# meca_2018.net
KiCad netlist of a schematic drawn in EAGLE
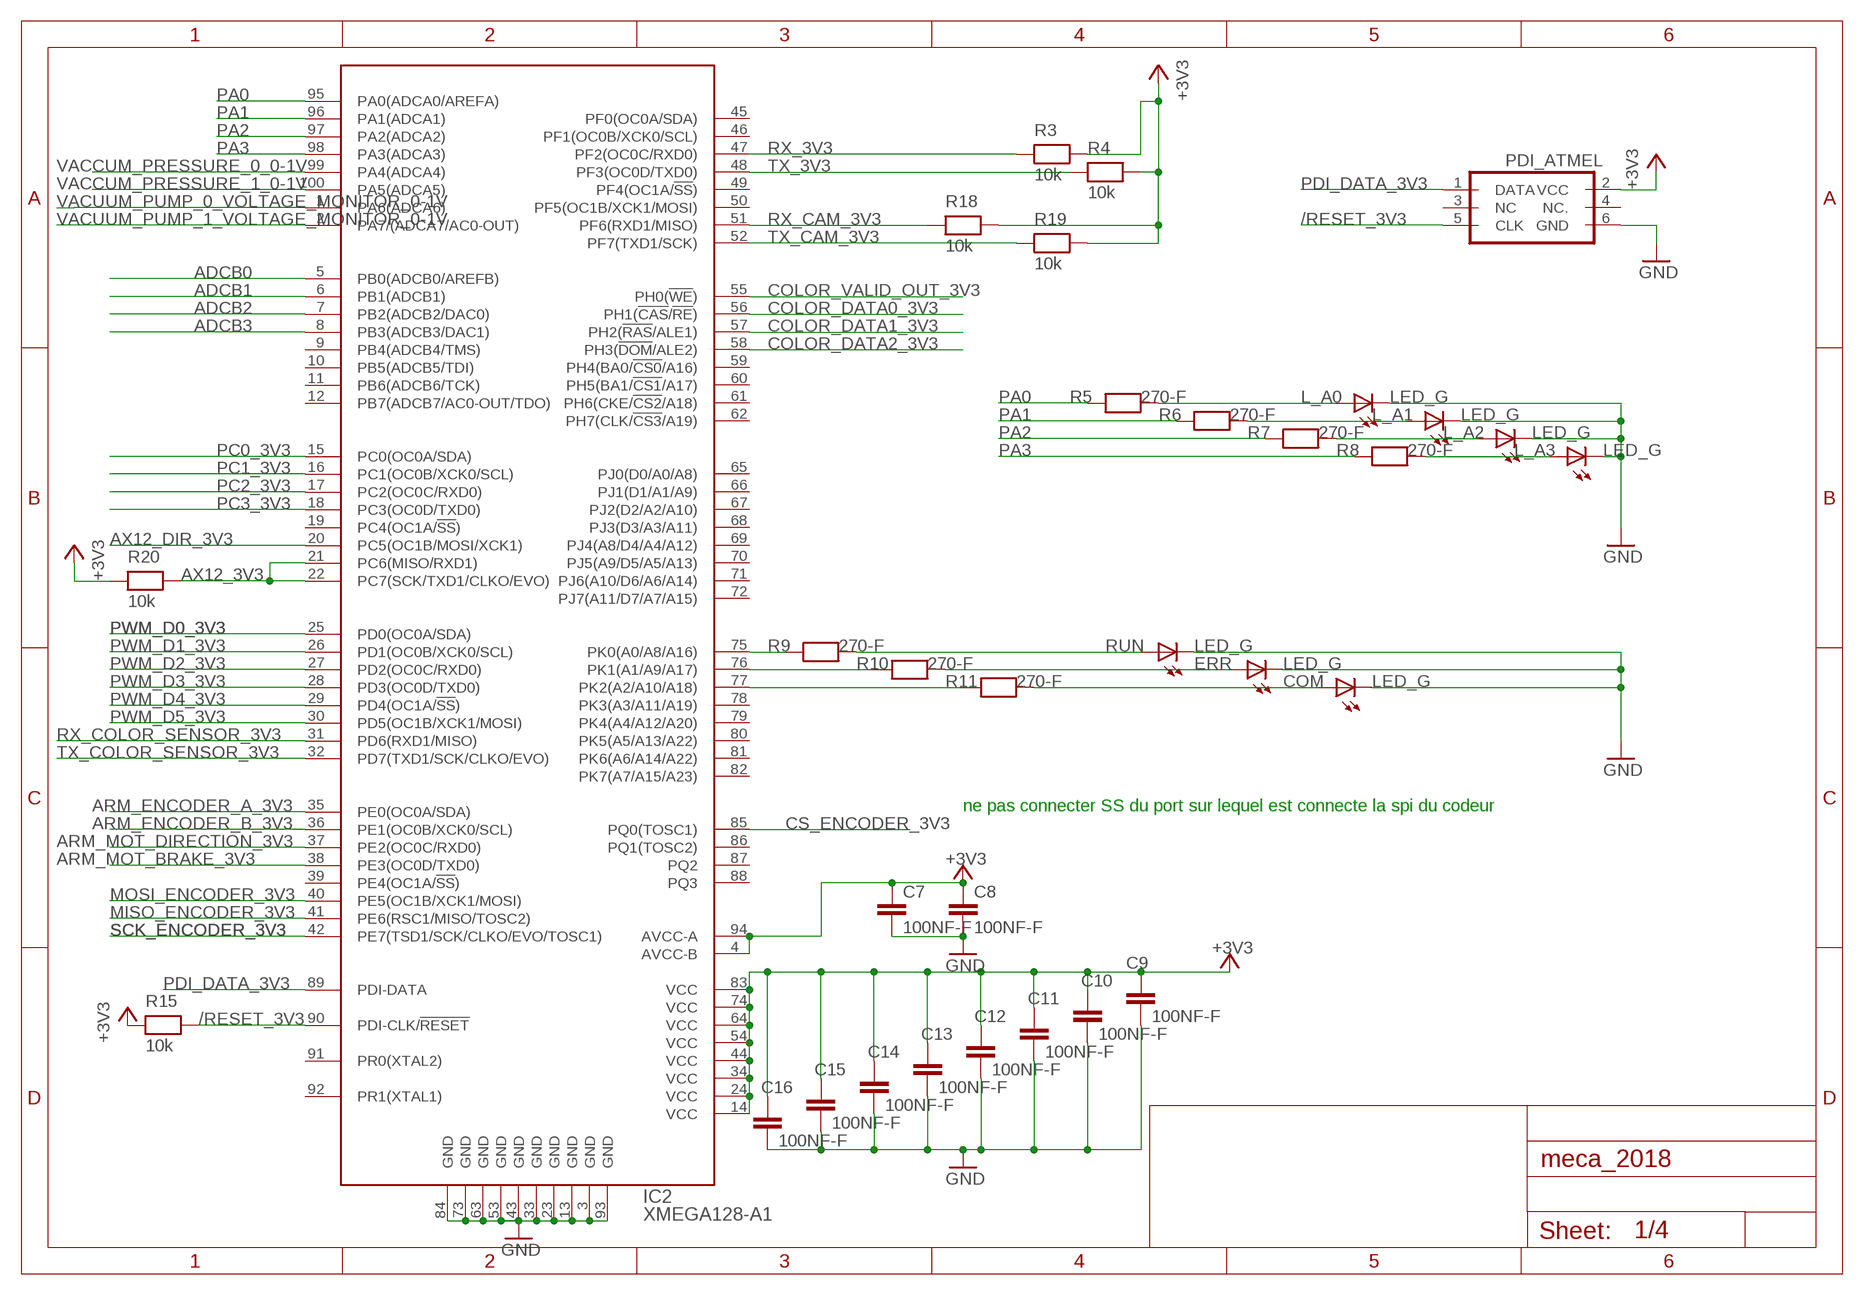
[diagram p0: schematic, sheet 1]
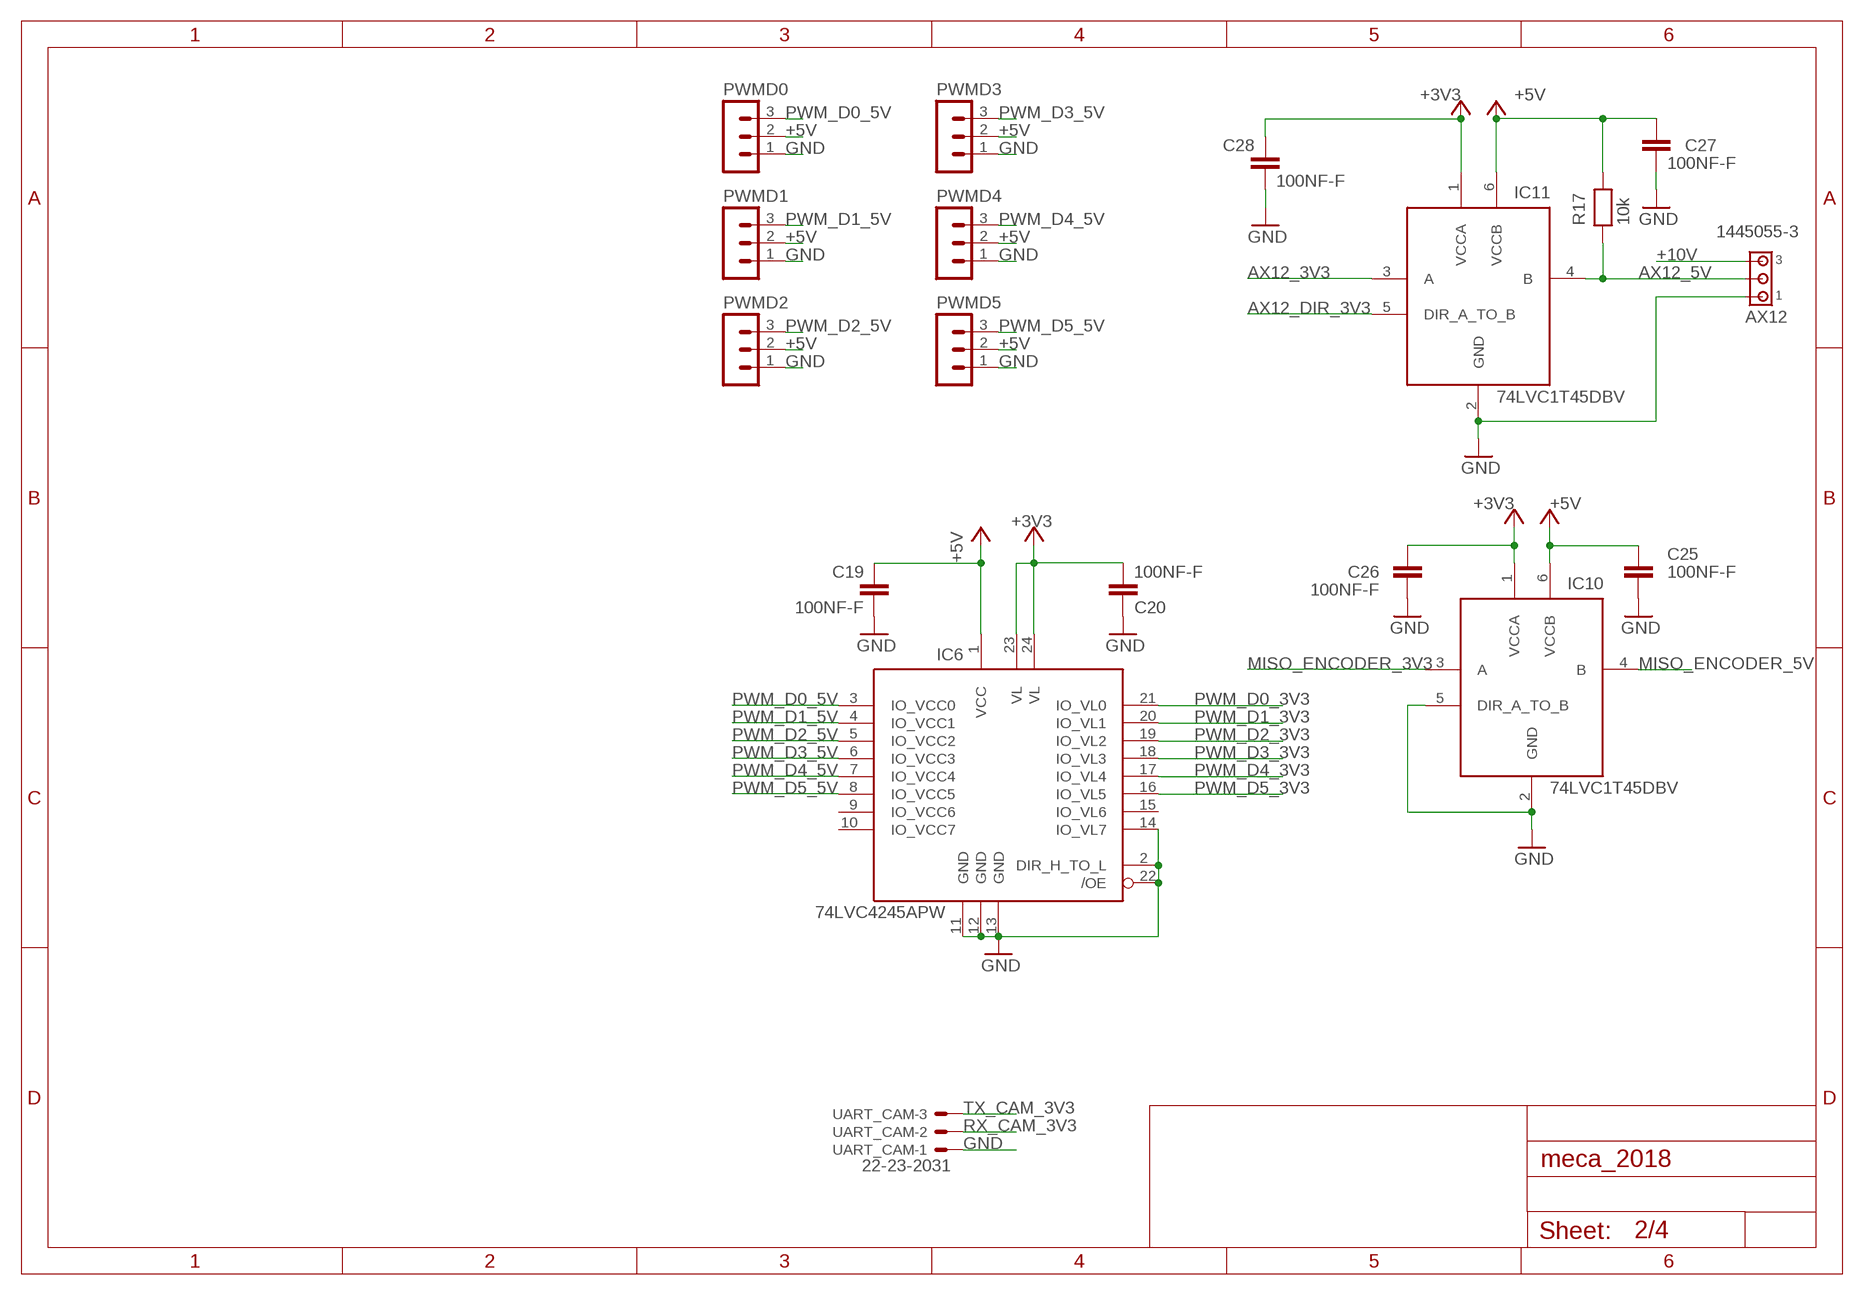
[diagram p1: schematic, sheet 2]
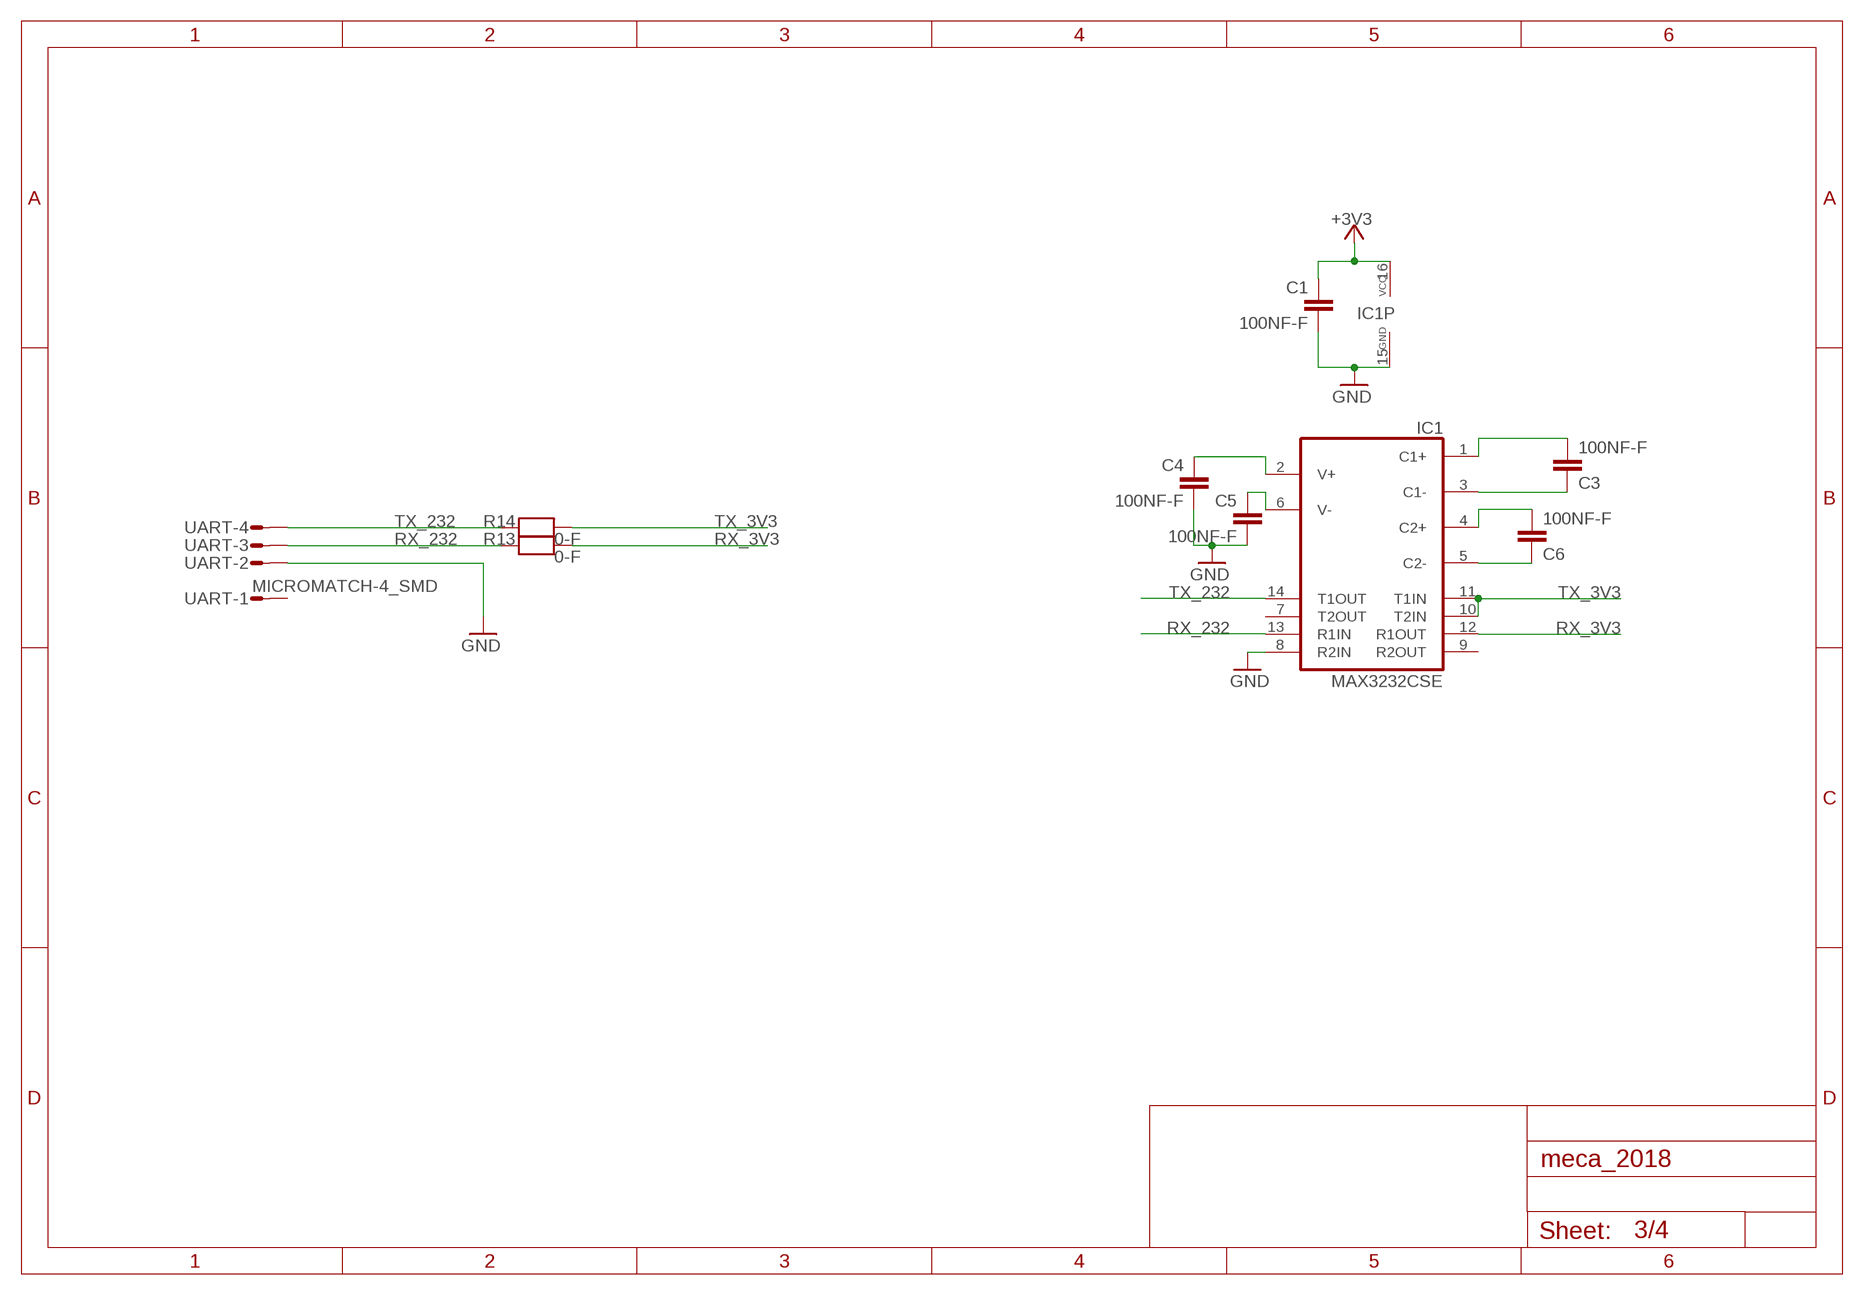
[diagram p2: schematic, sheet 3]
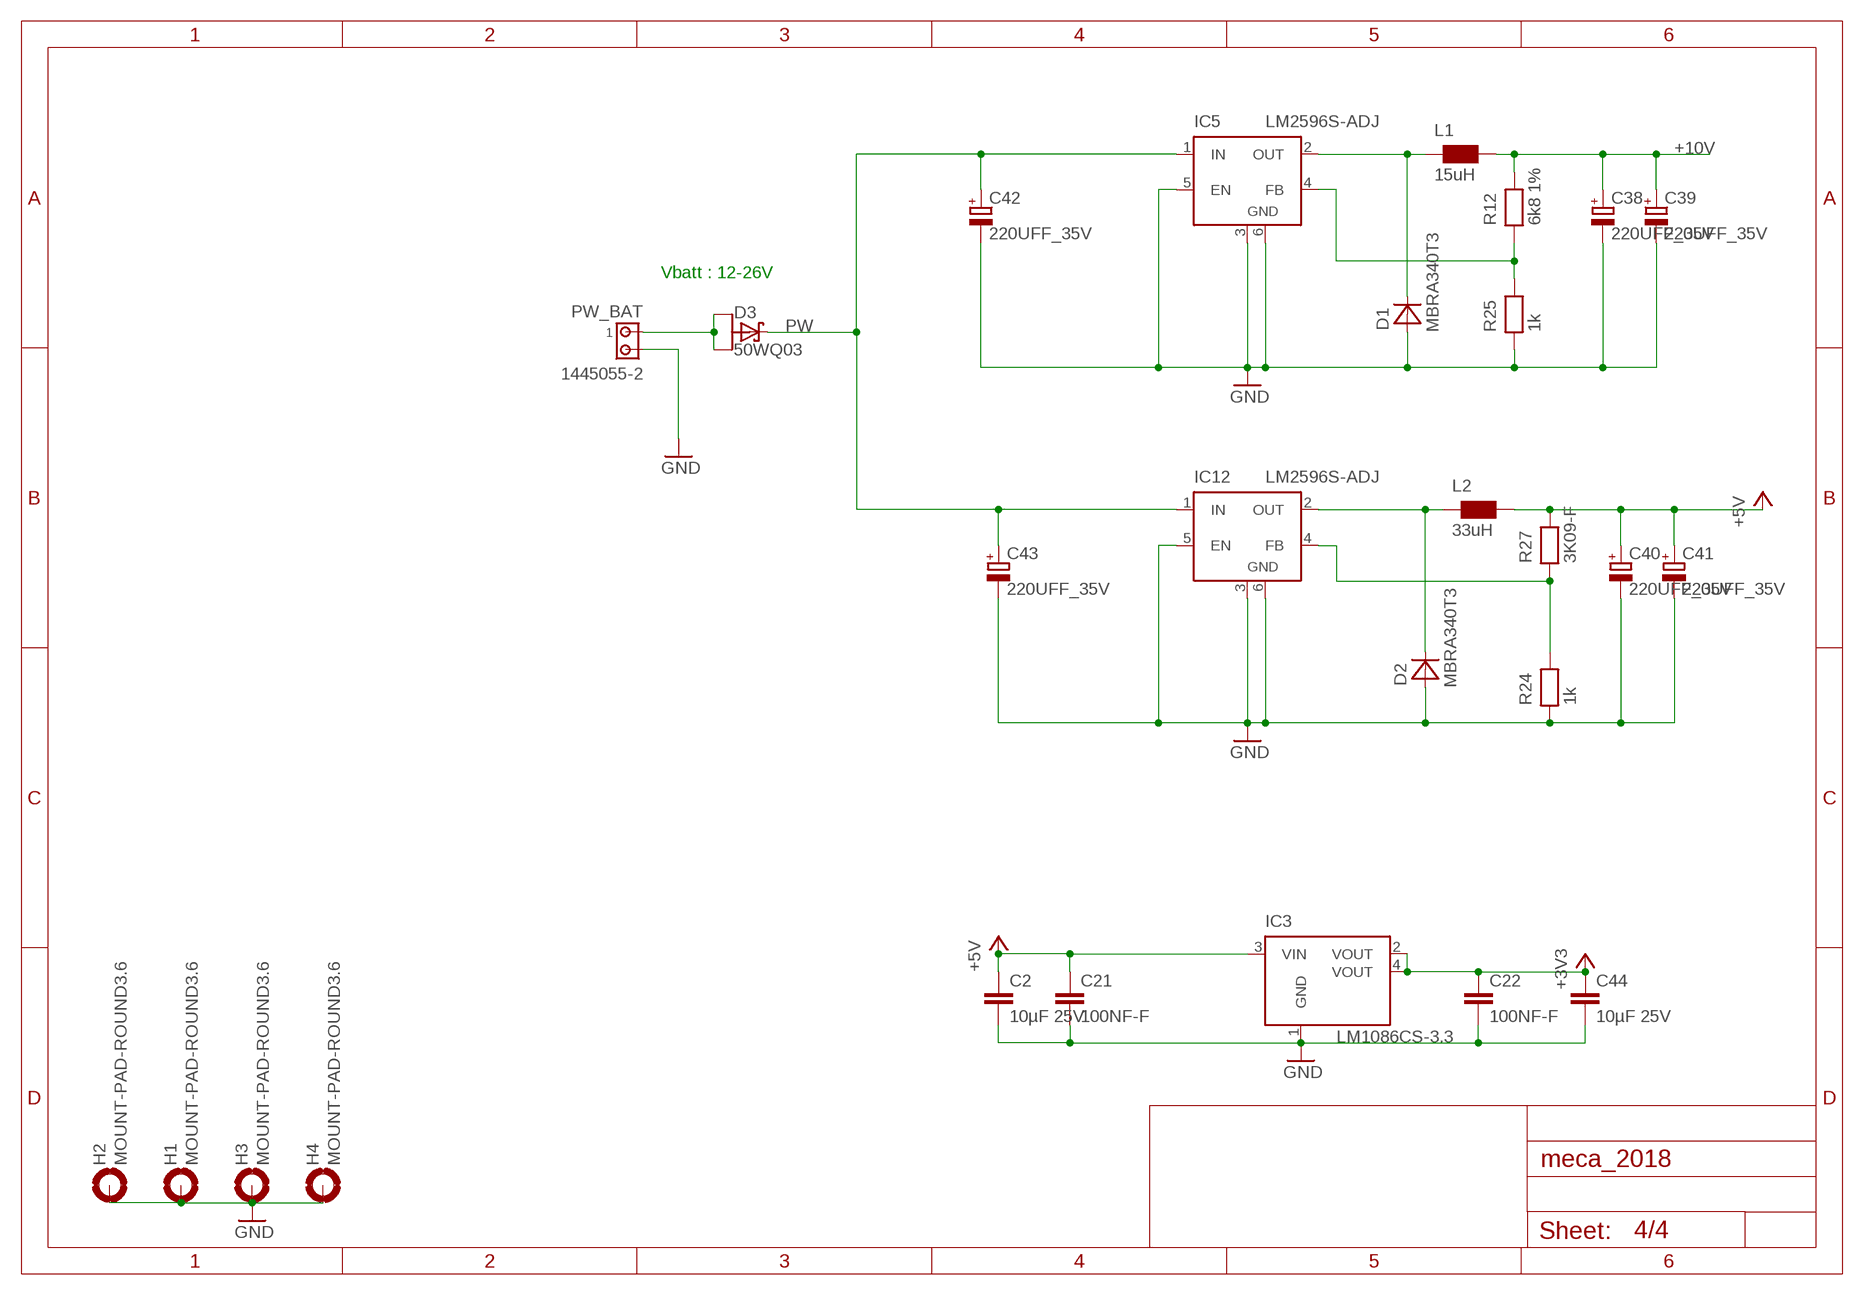
[diagram p3: schematic, sheet 4]

(export (version "E")
  (design (tool "Eeschema 10.0.6"))
  (components
    (comp (ref "C1")
      (value "100NF-F")
      (footprint "eagle-import:C0603")
      (libsource (lib "eagle-import") (part "100NF-F"))
    )
    (comp (ref "C3")
      (value "100NF-F")
      (footprint "eagle-import:C0603")
      (libsource (lib "eagle-import") (part "100NF-F"))
    )
    (comp (ref "C4")
      (value "100NF-F")
      (footprint "eagle-import:C0603")
      (libsource (lib "eagle-import") (part "100NF-F"))
    )
    (comp (ref "C5")
      (value "100NF-F")
      (footprint "eagle-import:C0603")
      (libsource (lib "eagle-import") (part "100NF-F"))
    )
    (comp (ref "C6")
      (value "100NF-F")
      (footprint "eagle-import:C0603")
      (libsource (lib "eagle-import") (part "100NF-F"))
    )
    (comp (ref "IC1")
      (value "MAX3232CSE")
      (footprint "eagle-import:SO16")
      (libsource (lib "eagle-import") (part "MAX3232SEC"))
    )
    (comp (ref "R13")
      (value "0-F")
      (footprint "eagle-import:R0603")
      (libsource (lib "eagle-import") (part "0-F"))
    )
    (comp (ref "R14")
      (value "0-F")
      (footprint "eagle-import:R0603")
      (libsource (lib "eagle-import") (part "0-F"))
    )
    (comp (ref "UART")
      (value "MICROMATCH-4_SMD")
      (footprint "eagle-import:MICROMATCH-4_SMD")
      (libsource (lib "eagle-import") (part "MICROMATCH-4_SMD"))
    )
    (comp (ref "C7")
      (value "100NF-F")
      (footprint "eagle-import:C0603")
      (libsource (lib "eagle-import") (part "100NF-F"))
    )
    (comp (ref "C8")
      (value "100NF-F")
      (footprint "eagle-import:C0603")
      (libsource (lib "eagle-import") (part "100NF-F"))
    )
    (comp (ref "C9")
      (value "100NF-F")
      (footprint "eagle-import:C0603")
      (libsource (lib "eagle-import") (part "100NF-F"))
    )
    (comp (ref "C10")
      (value "100NF-F")
      (footprint "eagle-import:C0603")
      (libsource (lib "eagle-import") (part "100NF-F"))
    )
    (comp (ref "C11")
      (value "100NF-F")
      (footprint "eagle-import:C0603")
      (libsource (lib "eagle-import") (part "100NF-F"))
    )
    (comp (ref "C12")
      (value "100NF-F")
      (footprint "eagle-import:C0603")
      (libsource (lib "eagle-import") (part "100NF-F"))
    )
    (comp (ref "C13")
      (value "100NF-F")
      (footprint "eagle-import:C0603")
      (libsource (lib "eagle-import") (part "100NF-F"))
    )
    (comp (ref "C14")
      (value "100NF-F")
      (footprint "eagle-import:C0603")
      (libsource (lib "eagle-import") (part "100NF-F"))
    )
    (comp (ref "C15")
      (value "100NF-F")
      (footprint "eagle-import:C0603")
      (libsource (lib "eagle-import") (part "100NF-F"))
    )
    (comp (ref "C16")
      (value "100NF-F")
      (footprint "eagle-import:C0603")
      (libsource (lib "eagle-import") (part "100NF-F"))
    )
    (comp (ref "COM")
      (value "LED_G")
      (footprint "eagle-import:CHIP-LED0805")
      (libsource (lib "eagle-import") (part "LED_G"))
    )
    (comp (ref "ERR")
      (value "LED_G")
      (footprint "eagle-import:CHIP-LED0805")
      (libsource (lib "eagle-import") (part "LED_G"))
    )
    (comp (ref "IC2")
      (value "XMEGA128-A1")
      (footprint "eagle-import:TQFP100")
      (libsource (lib "eagle-import") (part "XMEGA-A1TQFP"))
    )
    (comp (ref "L_A0")
      (value "LED_G")
      (footprint "eagle-import:CHIP-LED0805")
      (libsource (lib "eagle-import") (part "LED_G"))
    )
    (comp (ref "L_A1")
      (value "LED_G")
      (footprint "eagle-import:CHIP-LED0805")
      (libsource (lib "eagle-import") (part "LED_G"))
    )
    (comp (ref "L_A2")
      (value "LED_G")
      (footprint "eagle-import:CHIP-LED0805")
      (libsource (lib "eagle-import") (part "LED_G"))
    )
    (comp (ref "L_A3")
      (value "LED_G")
      (footprint "eagle-import:CHIP-LED0805")
      (libsource (lib "eagle-import") (part "LED_G"))
    )
    (comp (ref "PDI_ATMEL")
      (value "PDI_ATMEL")
      (footprint "eagle-import:ML6")
      (libsource (lib "eagle-import") (part "PDI_ATMEL"))
    )
    (comp (ref "R3")
      (value "10k")
      (footprint "eagle-import:R0603")
      (libsource (lib "eagle-import") (part "10K-F"))
    )
    (comp (ref "R4")
      (value "10k")
      (footprint "eagle-import:R0603")
      (libsource (lib "eagle-import") (part "10K-F"))
    )
    (comp (ref "R5")
      (value "270-F")
      (footprint "eagle-import:R0603")
      (libsource (lib "eagle-import") (part "270-F"))
    )
    (comp (ref "R6")
      (value "270-F")
      (footprint "eagle-import:R0603")
      (libsource (lib "eagle-import") (part "270-F"))
    )
    (comp (ref "R7")
      (value "270-F")
      (footprint "eagle-import:R0603")
      (libsource (lib "eagle-import") (part "270-F"))
    )
    (comp (ref "R8")
      (value "270-F")
      (footprint "eagle-import:R0603")
      (libsource (lib "eagle-import") (part "270-F"))
    )
    (comp (ref "R9")
      (value "270-F")
      (footprint "eagle-import:R0603")
      (libsource (lib "eagle-import") (part "270-F"))
    )
    (comp (ref "R10")
      (value "270-F")
      (footprint "eagle-import:R0603")
      (libsource (lib "eagle-import") (part "270-F"))
    )
    (comp (ref "R11")
      (value "270-F")
      (footprint "eagle-import:R0603")
      (libsource (lib "eagle-import") (part "270-F"))
    )
    (comp (ref "R15")
      (value "10k")
      (footprint "eagle-import:R0603")
      (libsource (lib "eagle-import") (part "10K-F"))
    )
    (comp (ref "R18")
      (value "10k")
      (footprint "eagle-import:R0603")
      (libsource (lib "eagle-import") (part "10K-F"))
    )
    (comp (ref "R19")
      (value "10k")
      (footprint "eagle-import:R0603")
      (libsource (lib "eagle-import") (part "10K-F"))
    )
    (comp (ref "R20")
      (value "10k")
      (footprint "eagle-import:R0603")
      (libsource (lib "eagle-import") (part "10K-F"))
    )
    (comp (ref "RUN")
      (value "LED_G")
      (footprint "eagle-import:CHIP-LED0805")
      (libsource (lib "eagle-import") (part "LED_G"))
    )
    (comp (ref "AX12")
      (value "1445055-3")
      (footprint "eagle-import:1445055-3")
      (libsource (lib "eagle-import") (part "1445055-3"))
    )
    (comp (ref "C19")
      (value "100NF-F")
      (footprint "eagle-import:C0603")
      (libsource (lib "eagle-import") (part "100NF-F"))
    )
    (comp (ref "C20")
      (value "100NF-F")
      (footprint "eagle-import:C0603")
      (libsource (lib "eagle-import") (part "100NF-F"))
    )
    (comp (ref "C25")
      (value "100NF-F")
      (footprint "eagle-import:C0603")
      (libsource (lib "eagle-import") (part "100NF-F"))
    )
    (comp (ref "C26")
      (value "100NF-F")
      (footprint "eagle-import:C0603")
      (libsource (lib "eagle-import") (part "100NF-F"))
    )
    (comp (ref "C27")
      (value "100NF-F")
      (footprint "eagle-import:C0603")
      (libsource (lib "eagle-import") (part "100NF-F"))
    )
    (comp (ref "C28")
      (value "100NF-F")
      (footprint "eagle-import:C0603")
      (libsource (lib "eagle-import") (part "100NF-F"))
    )
    (comp (ref "IC6")
      (value "74LVC4245APW")
      (footprint "eagle-import:TSSOP24")
      (libsource (lib "eagle-import") (part "74LVC4245APW"))
    )
    (comp (ref "IC10")
      (value "74LVC1T45DBV")
      (footprint "eagle-import:SOT23-6")
      (libsource (lib "eagle-import") (part "74LVC1T45DBV"))
    )
    (comp (ref "IC11")
      (value "74LVC1T45DBV")
      (footprint "eagle-import:SOT23-6")
      (libsource (lib "eagle-import") (part "74LVC1T45DBV"))
    )
    (comp (ref "PWMD0")
      (value "MA03-1")
      (footprint "eagle-import:MA03-1")
      (fields (field (name "OC_FARNELL") "unknown") (field (name "OC_NEWARK") "unknown"))
      (libsource (lib "eagle-import") (part "MA03-1"))
    )
    (comp (ref "PWMD1")
      (value "MA03-1")
      (footprint "eagle-import:MA03-1")
      (fields (field (name "OC_FARNELL") "unknown") (field (name "OC_NEWARK") "unknown"))
      (libsource (lib "eagle-import") (part "MA03-1"))
    )
    (comp (ref "PWMD2")
      (value "MA03-1")
      (footprint "eagle-import:MA03-1")
      (fields (field (name "OC_FARNELL") "unknown") (field (name "OC_NEWARK") "unknown"))
      (libsource (lib "eagle-import") (part "MA03-1"))
    )
    (comp (ref "PWMD3")
      (value "MA03-1")
      (footprint "eagle-import:MA03-1")
      (libsource (lib "eagle-import") (part "MA03-1"))
    )
    (comp (ref "PWMD4")
      (value "MA03-1")
      (footprint "eagle-import:MA03-1")
      (libsource (lib "eagle-import") (part "MA03-1"))
    )
    (comp (ref "PWMD5")
      (value "MA03-1")
      (footprint "eagle-import:MA03-1")
      (libsource (lib "eagle-import") (part "MA03-1"))
    )
    (comp (ref "R17")
      (value "10k")
      (footprint "eagle-import:R0603")
      (libsource (lib "eagle-import") (part "10K-F"))
    )
    (comp (ref "UART_CAM")
      (value "22-23-2031")
      (footprint "eagle-import:22-23-2031")
      (fields (field (name "MF") "MOLEX"))
      (libsource (lib "eagle-import") (part "22-23-2031"))
    )
    (comp (ref "C2")
      (value "10µF 25V")
      (footprint "eagle-import:C1210")
      (libsource (lib "eagle-import") (part "10UF-C_25V"))
    )
    (comp (ref "C21")
      (value "100NF-F")
      (footprint "eagle-import:C0603")
      (libsource (lib "eagle-import") (part "100NF-F"))
    )
    (comp (ref "C22")
      (value "100NF-F")
      (footprint "eagle-import:C0603")
      (libsource (lib "eagle-import") (part "100NF-F"))
    )
    (comp (ref "C38")
      (value "220UFF_35V")
      (footprint "eagle-import:PANASONIC_F")
      (libsource (lib "eagle-import") (part "220UFF_35V"))
    )
    (comp (ref "C39")
      (value "220UFF_35V")
      (footprint "eagle-import:PANASONIC_F")
      (libsource (lib "eagle-import") (part "220UFF_35V"))
    )
    (comp (ref "C40")
      (value "220UFF_35V")
      (footprint "eagle-import:PANASONIC_F")
      (libsource (lib "eagle-import") (part "220UFF_35V"))
    )
    (comp (ref "C41")
      (value "220UFF_35V")
      (footprint "eagle-import:PANASONIC_F")
      (libsource (lib "eagle-import") (part "220UFF_35V"))
    )
    (comp (ref "C42")
      (value "220UFF_35V")
      (footprint "eagle-import:PANASONIC_F")
      (libsource (lib "eagle-import") (part "220UFF_35V"))
    )
    (comp (ref "C43")
      (value "220UFF_35V")
      (footprint "eagle-import:PANASONIC_F")
      (libsource (lib "eagle-import") (part "220UFF_35V"))
    )
    (comp (ref "C44")
      (value "10µF 25V")
      (footprint "eagle-import:C1210")
      (libsource (lib "eagle-import") (part "10UF-C_25V"))
    )
    (comp (ref "D1")
      (value "MBRA340T3")
      (footprint "eagle-import:SMA")
      (libsource (lib "eagle-import") (part "MBRA340T3"))
    )
    (comp (ref "D2")
      (value "MBRA340T3")
      (footprint "eagle-import:SMA")
      (libsource (lib "eagle-import") (part "MBRA340T3"))
    )
    (comp (ref "D3")
      (value "50WQ03")
      (footprint "eagle-import:TO252")
      (libsource (lib "eagle-import") (part "50WQ03"))
    )
    (comp (ref "H1")
      (value "MOUNT-PAD-ROUND3.6")
      (footprint "eagle-import:3,6-PAD")
      (libsource (lib "eagle-import") (part "MOUNT-PAD-ROUND3.6"))
    )
    (comp (ref "H2")
      (value "MOUNT-PAD-ROUND3.6")
      (footprint "eagle-import:3,6-PAD")
      (libsource (lib "eagle-import") (part "MOUNT-PAD-ROUND3.6"))
    )
    (comp (ref "H3")
      (value "MOUNT-PAD-ROUND3.6")
      (footprint "eagle-import:3,6-PAD")
      (libsource (lib "eagle-import") (part "MOUNT-PAD-ROUND3.6"))
    )
    (comp (ref "H4")
      (value "MOUNT-PAD-ROUND3.6")
      (footprint "eagle-import:3,6-PAD")
      (libsource (lib "eagle-import") (part "MOUNT-PAD-ROUND3.6"))
    )
    (comp (ref "IC3")
      (value "LM1086CS-3.3")
      (footprint "eagle-import:TO263")
      (libsource (lib "eagle-import") (part "LM1086CS-3.3"))
    )
    (comp (ref "IC5")
      (value "LM2596S-ADJ")
      (footprint "eagle-import:TO263-5")
      (libsource (lib "eagle-import") (part "LM2596S-ADJ"))
    )
    (comp (ref "IC12")
      (value "LM2596S-ADJ")
      (footprint "eagle-import:TO263-5")
      (libsource (lib "eagle-import") (part "LM2596S-ADJ"))
    )
    (comp (ref "L1")
      (value "15uH")
      (footprint "eagle-import:SRR1280")
      (libsource (lib "eagle-import") (part "SRR1280-150"))
    )
    (comp (ref "L2")
      (value "33uH")
      (footprint "eagle-import:SRR1280")
      (libsource (lib "eagle-import") (part "33µH-3.3A"))
    )
    (comp (ref "PW_BAT")
      (value "1445055-2")
      (footprint "eagle-import:1445055-2")
      (libsource (lib "eagle-import") (part "1445055-2"))
    )
    (comp (ref "R12")
      (value "6k8 1%")
      (footprint "eagle-import:R0603")
      (libsource (lib "eagle-import") (part "6K8-F"))
    )
    (comp (ref "R24")
      (value "1k")
      (footprint "eagle-import:R0603")
      (libsource (lib "eagle-import") (part "1K-F"))
    )
    (comp (ref "R25")
      (value "1k")
      (footprint "eagle-import:R0603")
      (libsource (lib "eagle-import") (part "1K-F"))
    )
    (comp (ref "R27")
      (value "3K09-F")
      (footprint "eagle-import:R0603")
      (libsource (lib "eagle-import") (part "3K09-F"))
    )
  )
  (nets
    (net (code "1") (name "+3V3") (class "Default")
      (node (ref "C1") (pin "1") (pinfunction "1_1") (pintype "passive"))
      (node (ref "C10") (pin "1") (pinfunction "1_1") (pintype "passive"))
      (node (ref "C11") (pin "1") (pinfunction "1_1") (pintype "passive"))
      (node (ref "C12") (pin "1") (pinfunction "1_1") (pintype "passive"))
      (node (ref "C13") (pin "1") (pinfunction "1_1") (pintype "passive"))
      (node (ref "C14") (pin "1") (pinfunction "1_1") (pintype "passive"))
      (node (ref "C15") (pin "1") (pinfunction "1_1") (pintype "passive"))
      (node (ref "C16") (pin "1") (pinfunction "1_1") (pintype "passive"))
      (node (ref "C20") (pin "1") (pinfunction "1_1") (pintype "passive"))
      (node (ref "C22") (pin "1") (pinfunction "1_1") (pintype "passive"))
      (node (ref "C26") (pin "1") (pinfunction "1_1") (pintype "passive"))
      (node (ref "C28") (pin "1") (pinfunction "1_1") (pintype "passive"))
      (node (ref "C44") (pin "1") (pinfunction "1_1") (pintype "passive"))
      (node (ref "C7") (pin "1") (pinfunction "1_1") (pintype "passive"))
      (node (ref "C8") (pin "1") (pinfunction "1_1") (pintype "passive"))
      (node (ref "C9") (pin "1") (pinfunction "1_1") (pintype "passive"))
      (node (ref "IC1") (pin "16") (pinfunction "VCC_16") (pintype "power_in"))
      (node (ref "IC10") (pin "1") (pinfunction "VCCA_1") (pintype "power_in"))
      (node (ref "IC11") (pin "1") (pinfunction "VCCA_1") (pintype "power_in"))
      (node (ref "IC2") (pin "14") (pinfunction "VCC_14") (pintype "power_in"))
      (node (ref "IC2") (pin "24") (pinfunction "VCC_24") (pintype "power_in"))
      (node (ref "IC2") (pin "34") (pinfunction "VCC_34") (pintype "power_in"))
      (node (ref "IC2") (pin "4") (pinfunction "AVCC-B_4") (pintype "power_in"))
      (node (ref "IC2") (pin "44") (pinfunction "VCC_44") (pintype "power_in"))
      (node (ref "IC2") (pin "54") (pinfunction "VCC_54") (pintype "power_in"))
      (node (ref "IC2") (pin "64") (pinfunction "VCC_64") (pintype "power_in"))
      (node (ref "IC2") (pin "74") (pinfunction "VCC_74") (pintype "power_in"))
      (node (ref "IC2") (pin "83") (pinfunction "VCC_83") (pintype "power_in"))
      (node (ref "IC2") (pin "94") (pinfunction "AVCC-A_94") (pintype "power_in"))
      (node (ref "IC3") (pin "2") (pinfunction "VOUT_2") (pintype "bidirectional"))
      (node (ref "IC3") (pin "4") (pinfunction "VOUT_4") (pintype "bidirectional"))
      (node (ref "IC6") (pin "23") (pinfunction "VL_23") (pintype "power_in"))
      (node (ref "IC6") (pin "24") (pinfunction "VL_24") (pintype "power_in"))
      (node (ref "PDI_ATMEL") (pin "2") (pinfunction "VCC_2") (pintype "passive"))
      (node (ref "R15") (pin "1") (pinfunction "1_1") (pintype "bidirectional"))
      (node (ref "R18") (pin "2") (pinfunction "2_2") (pintype "bidirectional"))
      (node (ref "R19") (pin "2") (pinfunction "2_2") (pintype "bidirectional"))
      (node (ref "R20") (pin "1") (pinfunction "1_1") (pintype "bidirectional"))
      (node (ref "R3") (pin "2") (pinfunction "2_2") (pintype "bidirectional"))
      (node (ref "R4") (pin "2") (pinfunction "2_2") (pintype "bidirectional"))
    )
    (net (code "2") (name "+5V") (class "Default")
      (node (ref "C19") (pin "1") (pinfunction "1_1") (pintype "passive"))
      (node (ref "C2") (pin "1") (pinfunction "1_1") (pintype "passive"))
      (node (ref "C21") (pin "1") (pinfunction "1_1") (pintype "passive"))
      (node (ref "C25") (pin "1") (pinfunction "1_1") (pintype "passive"))
      (node (ref "C27") (pin "1") (pinfunction "1_1") (pintype "passive"))
      (node (ref "C40") (pin "+") (pinfunction "+_+") (pintype "passive"))
      (node (ref "C41") (pin "+") (pinfunction "+_+") (pintype "passive"))
      (node (ref "IC10") (pin "6") (pinfunction "VCCB_6") (pintype "power_in"))
      (node (ref "IC11") (pin "6") (pinfunction "VCCB_6") (pintype "power_in"))
      (node (ref "IC3") (pin "3") (pinfunction "VIN_3") (pintype "bidirectional"))
      (node (ref "IC6") (pin "1") (pinfunction "VCC_1") (pintype "power_in"))
      (node (ref "L2") (pin "2") (pinfunction "2_2") (pintype "passive"))
      (node (ref "PWMD0") (pin "2") (pinfunction "2_2") (pintype "passive"))
      (node (ref "PWMD1") (pin "2") (pinfunction "2_2") (pintype "passive"))
      (node (ref "PWMD2") (pin "2") (pinfunction "2_2") (pintype "passive"))
      (node (ref "PWMD3") (pin "2") (pinfunction "2_2") (pintype "passive"))
      (node (ref "PWMD4") (pin "2") (pinfunction "2_2") (pintype "passive"))
      (node (ref "PWMD5") (pin "2") (pinfunction "2_2") (pintype "passive"))
      (node (ref "R17") (pin "2") (pinfunction "2_2") (pintype "bidirectional"))
      (node (ref "R27") (pin "2") (pinfunction "2_2") (pintype "bidirectional"))
    )
    (net (code "3") (name "+10V") (class "Default")
      (node (ref "AX12") (pin "3") (pinfunction "3_3") (pintype "passive"))
      (node (ref "C38") (pin "+") (pinfunction "+_+") (pintype "passive"))
      (node (ref "C39") (pin "+") (pinfunction "+_+") (pintype "passive"))
      (node (ref "L1") (pin "2") (pinfunction "2_2") (pintype "passive"))
      (node (ref "R12") (pin "2") (pinfunction "2_2") (pintype "bidirectional"))
    )
    (net (code "4") (name "ADCB0") (class "Default")
      (node (ref "IC2") (pin "5") (pinfunction "PB0(ADCB0/AREFB)_5") (pintype "bidirectional"))
    )
    (net (code "5") (name "ADCB1") (class "Default")
      (node (ref "IC2") (pin "6") (pinfunction "PB1(ADCB1)_6") (pintype "bidirectional"))
    )
    (net (code "6") (name "ADCB2") (class "Default")
      (node (ref "IC2") (pin "7") (pinfunction "PB2(ADCB2/DAC0)_7") (pintype "bidirectional"))
    )
    (net (code "7") (name "ADCB3") (class "Default")
      (node (ref "IC2") (pin "8") (pinfunction "PB3(ADCB3/DAC1)_8") (pintype "bidirectional"))
    )
    (net (code "8") (name "ARM_ENCODER_A_3V3") (class "Default")
      (node (ref "IC2") (pin "35") (pinfunction "PE0(OC0A/SDA)_35") (pintype "bidirectional"))
    )
    (net (code "9") (name "ARM_ENCODER_B_3V3") (class "Default")
      (node (ref "IC2") (pin "36") (pinfunction "PE1(OC0B/XCK0/SCL)_36") (pintype "bidirectional"))
    )
    (net (code "10") (name "ARM_MOT_BRAKE_3V3") (class "Default")
      (node (ref "IC2") (pin "38") (pinfunction "PE3(OC0D/TXD0)_38") (pintype "bidirectional"))
    )
    (net (code "11") (name "ARM_MOT_DIRECTION_3V3") (class "Default")
      (node (ref "IC2") (pin "37") (pinfunction "PE2(OC0C/RXD0)_37") (pintype "bidirectional"))
    )
    (net (code "12") (name "AX12_3V3") (class "Default")
      (node (ref "IC11") (pin "3") (pinfunction "A_3") (pintype "bidirectional"))
      (node (ref "IC2") (pin "21") (pinfunction "PC6(MISO/RXD1)_21") (pintype "bidirectional"))
      (node (ref "IC2") (pin "22") (pinfunction "PC7(SCK/TXD1/CLKO/EVO)_22") (pintype "bidirectional"))
      (node (ref "R20") (pin "2") (pinfunction "2_2") (pintype "bidirectional"))
    )
    (net (code "13") (name "AX12_5V") (class "Default")
      (node (ref "AX12") (pin "2") (pinfunction "2_2") (pintype "passive"))
      (node (ref "IC11") (pin "4") (pinfunction "B_4") (pintype "bidirectional"))
      (node (ref "R17") (pin "1") (pinfunction "1_1") (pintype "bidirectional"))
    )
    (net (code "14") (name "AX12_DIR_3V3") (class "Default")
      (node (ref "IC11") (pin "5") (pinfunction "DIR_A_TO_B_5") (pintype "bidirectional"))
      (node (ref "IC2") (pin "20") (pinfunction "PC5(OC1B/MOSI/XCK1)_20") (pintype "bidirectional"))
    )
    (net (code "15") (name "COLOR_DATA0_3V3") (class "Default")
      (node (ref "IC2") (pin "56") (pinfunction "PH1(~{CAS}/~{RE})_56") (pintype "bidirectional"))
    )
    (net (code "16") (name "COLOR_DATA1_3V3") (class "Default")
      (node (ref "IC2") (pin "57") (pinfunction "PH2(~{RAS}/ALE1)_57") (pintype "bidirectional"))
    )
    (net (code "17") (name "COLOR_DATA2_3V3") (class "Default")
      (node (ref "IC2") (pin "58") (pinfunction "PH3(~{DOM}/ALE2)_58") (pintype "bidirectional"))
    )
    (net (code "18") (name "COLOR_VALID_OUT_3V3") (class "Default")
      (node (ref "IC2") (pin "55") (pinfunction "PH0(~{WE})_55") (pintype "bidirectional"))
    )
    (net (code "19") (name "CS_ENCODER_3V3") (class "Default")
      (node (ref "IC2") (pin "85") (pinfunction "PQ0(TOSC1)_85") (pintype "bidirectional"))
    )
    (net (code "20") (name "GND") (class "Default")
      (node (ref "AX12") (pin "1") (pinfunction "1_1") (pintype "passive"))
      (node (ref "C1") (pin "2") (pinfunction "2_2") (pintype "passive"))
      (node (ref "C10") (pin "2") (pinfunction "2_2") (pintype "passive"))
      (node (ref "C11") (pin "2") (pinfunction "2_2") (pintype "passive"))
      (node (ref "C12") (pin "2") (pinfunction "2_2") (pintype "passive"))
      (node (ref "C13") (pin "2") (pinfunction "2_2") (pintype "passive"))
      (node (ref "C14") (pin "2") (pinfunction "2_2") (pintype "passive"))
      (node (ref "C15") (pin "2") (pinfunction "2_2") (pintype "passive"))
      (node (ref "C16") (pin "2") (pinfunction "2_2") (pintype "passive"))
      (node (ref "C19") (pin "2") (pinfunction "2_2") (pintype "passive"))
      (node (ref "C2") (pin "2") (pinfunction "2_2") (pintype "passive"))
      (node (ref "C20") (pin "2") (pinfunction "2_2") (pintype "passive"))
      (node (ref "C21") (pin "2") (pinfunction "2_2") (pintype "passive"))
      (node (ref "C22") (pin "2") (pinfunction "2_2") (pintype "passive"))
      (node (ref "C25") (pin "2") (pinfunction "2_2") (pintype "passive"))
      (node (ref "C26") (pin "2") (pinfunction "2_2") (pintype "passive"))
      (node (ref "C27") (pin "2") (pinfunction "2_2") (pintype "passive"))
      (node (ref "C28") (pin "2") (pinfunction "2_2") (pintype "passive"))
      (node (ref "C38") (pin "-") (pinfunction "-_-") (pintype "passive"))
      (node (ref "C39") (pin "-") (pinfunction "-_-") (pintype "passive"))
      (node (ref "C4") (pin "2") (pinfunction "2_2") (pintype "passive"))
      (node (ref "C40") (pin "-") (pinfunction "-_-") (pintype "passive"))
      (node (ref "C41") (pin "-") (pinfunction "-_-") (pintype "passive"))
      (node (ref "C42") (pin "-") (pinfunction "-_-") (pintype "passive"))
      (node (ref "C43") (pin "-") (pinfunction "-_-") (pintype "passive"))
      (node (ref "C44") (pin "2") (pinfunction "2_2") (pintype "passive"))
      (node (ref "C5") (pin "2") (pinfunction "2_2") (pintype "passive"))
      (node (ref "C7") (pin "2") (pinfunction "2_2") (pintype "passive"))
      (node (ref "C8") (pin "2") (pinfunction "2_2") (pintype "passive"))
      (node (ref "C9") (pin "2") (pinfunction "2_2") (pintype "passive"))
      (node (ref "COM") (pin "C") (pinfunction "C_C") (pintype "passive"))
      (node (ref "D1") (pin "A") (pinfunction "A_A") (pintype "passive"))
      (node (ref "D2") (pin "A") (pinfunction "A_A") (pintype "passive"))
      (node (ref "ERR") (pin "C") (pinfunction "C_C") (pintype "passive"))
      (node (ref "H1") (pin "B3,6") (pinfunction "MOUNT_B3,6") (pintype "passive"))
      (node (ref "H2") (pin "B3,6") (pinfunction "MOUNT_B3,6") (pintype "passive"))
      (node (ref "H3") (pin "B3,6") (pinfunction "MOUNT_B3,6") (pintype "passive"))
      (node (ref "H4") (pin "B3,6") (pinfunction "MOUNT_B3,6") (pintype "passive"))
      (node (ref "IC1") (pin "15") (pinfunction "GND_15") (pintype "power_in"))
      (node (ref "IC1") (pin "8") (pinfunction "R2IN_8") (pintype "input"))
      (node (ref "IC10") (pin "2") (pinfunction "GND_2") (pintype "power_in"))
      (node (ref "IC10") (pin "5") (pinfunction "DIR_A_TO_B_5") (pintype "bidirectional"))
      (node (ref "IC11") (pin "2") (pinfunction "GND_2") (pintype "power_in"))
      (node (ref "IC12") (pin "3") (pinfunction "GND_3") (pintype "power_in"))
      (node (ref "IC12") (pin "5") (pinfunction "EN_5") (pintype "input"))
      (node (ref "IC12") (pin "6") (pinfunction "GND_6") (pintype "power_in"))
      (node (ref "IC2") (pin "13") (pinfunction "GND_13") (pintype "power_in"))
      (node (ref "IC2") (pin "23") (pinfunction "GND_23") (pintype "power_in"))
      (node (ref "IC2") (pin "3") (pinfunction "GND_3") (pintype "power_in"))
      (node (ref "IC2") (pin "33") (pinfunction "GND_33") (pintype "power_in"))
      (node (ref "IC2") (pin "43") (pinfunction "GND_43") (pintype "power_in"))
      (node (ref "IC2") (pin "53") (pinfunction "GND_53") (pintype "power_in"))
      (node (ref "IC2") (pin "63") (pinfunction "GND_63") (pintype "power_in"))
      (node (ref "IC2") (pin "73") (pinfunction "GND_73") (pintype "power_in"))
      (node (ref "IC2") (pin "84") (pinfunction "GND_84") (pintype "power_in"))
      (node (ref "IC2") (pin "93") (pinfunction "GND_93") (pintype "power_in"))
      (node (ref "IC3") (pin "1") (pinfunction "GND_1") (pintype "bidirectional"))
      (node (ref "IC5") (pin "3") (pinfunction "GND_3") (pintype "power_in"))
      (node (ref "IC5") (pin "5") (pinfunction "EN_5") (pintype "input"))
      (node (ref "IC5") (pin "6") (pinfunction "GND_6") (pintype "power_in"))
      (node (ref "IC6") (pin "11") (pinfunction "GND_11") (pintype "power_in"))
      (node (ref "IC6") (pin "12") (pinfunction "GND_12") (pintype "power_in"))
      (node (ref "IC6") (pin "13") (pinfunction "GND_13") (pintype "power_in"))
      (node (ref "IC6") (pin "14") (pinfunction "IO_VL7_14") (pintype "bidirectional"))
      (node (ref "IC6") (pin "2") (pinfunction "DIR_H_TO_L_2") (pintype "bidirectional"))
      (node (ref "IC6") (pin "22") (pinfunction "/OE_22") (pintype "bidirectional"))
      (node (ref "L_A0") (pin "C") (pinfunction "C_C") (pintype "passive"))
      (node (ref "L_A1") (pin "C") (pinfunction "C_C") (pintype "passive"))
      (node (ref "L_A2") (pin "C") (pinfunction "C_C") (pintype "passive"))
      (node (ref "L_A3") (pin "C") (pinfunction "C_C") (pintype "passive"))
      (node (ref "PDI_ATMEL") (pin "6") (pinfunction "GND_6") (pintype "passive"))
      (node (ref "PWMD0") (pin "1") (pinfunction "1_1") (pintype "passive"))
      (node (ref "PWMD1") (pin "1") (pinfunction "1_1") (pintype "passive"))
      (node (ref "PWMD2") (pin "1") (pinfunction "1_1") (pintype "passive"))
      (node (ref "PWMD3") (pin "1") (pinfunction "1_1") (pintype "passive"))
      (node (ref "PWMD4") (pin "1") (pinfunction "1_1") (pintype "passive"))
      (node (ref "PWMD5") (pin "1") (pinfunction "1_1") (pintype "passive"))
      (node (ref "PW_BAT") (pin "2") (pinfunction "2_2") (pintype "passive"))
      (node (ref "R24") (pin "1") (pinfunction "1_1") (pintype "bidirectional"))
      (node (ref "R25") (pin "1") (pinfunction "1_1") (pintype "bidirectional"))
      (node (ref "RUN") (pin "C") (pinfunction "C_C") (pintype "passive"))
      (node (ref "UART") (pin "2") (pinfunction "S_2") (pintype "passive"))
      (node (ref "UART_CAM") (pin "1") (pinfunction "S_1") (pintype "passive"))
    )
    (net (code "21") (name "MISO_ENCODER_3V3") (class "Default")
      (node (ref "IC10") (pin "3") (pinfunction "A_3") (pintype "bidirectional"))
      (node (ref "IC2") (pin "41") (pinfunction "PE6(RSC1/MISO/TOSC2)_41") (pintype "bidirectional"))
    )
    (net (code "22") (name "MISO_ENCODER_5V") (class "Default")
      (node (ref "IC10") (pin "4") (pinfunction "B_4") (pintype "bidirectional"))
    )
    (net (code "23") (name "MOSI_ENCODER_3V3") (class "Default")
      (node (ref "IC2") (pin "40") (pinfunction "PE5(OC1B/XCK1/MOSI)_40") (pintype "bidirectional"))
    )
    (net (code "24") (name "Net-(COM-PadA)") (class "Default")
      (node (ref "COM") (pin "A") (pinfunction "A_A") (pintype "passive"))
      (node (ref "R11") (pin "2") (pinfunction "2_2") (pintype "bidirectional"))
    )
    (net (code "25") (name "Net-(D3-A1)") (class "Default")
      (node (ref "D3") (pin "1") (pinfunction "A1_1") (pintype "passive"))
      (node (ref "D3") (pin "3") (pinfunction "A2_3") (pintype "passive"))
      (node (ref "PW_BAT") (pin "1") (pinfunction "1_1") (pintype "passive"))
    )
    (net (code "26") (name "Net-(ERR-PadA)") (class "Default")
      (node (ref "ERR") (pin "A") (pinfunction "A_A") (pintype "passive"))
      (node (ref "R10") (pin "2") (pinfunction "2_2") (pintype "bidirectional"))
    )
    (net (code "27") (name "Net-(IC1A-C1+)") (class "Default")
      (node (ref "C3") (pin "1") (pinfunction "1_1") (pintype "passive"))
      (node (ref "IC1") (pin "1") (pinfunction "C1+_1") (pintype "bidirectional"))
    )
    (net (code "28") (name "Net-(IC1A-C1-)") (class "Default")
      (node (ref "C3") (pin "2") (pinfunction "2_2") (pintype "passive"))
      (node (ref "IC1") (pin "3") (pinfunction "C1-_3") (pintype "bidirectional"))
    )
    (net (code "29") (name "Net-(IC1A-C2+)") (class "Default")
      (node (ref "C6") (pin "1") (pinfunction "1_1") (pintype "passive"))
      (node (ref "IC1") (pin "4") (pinfunction "C2+_4") (pintype "bidirectional"))
    )
    (net (code "30") (name "Net-(IC1A-C2-)") (class "Default")
      (node (ref "C6") (pin "2") (pinfunction "2_2") (pintype "passive"))
      (node (ref "IC1") (pin "5") (pinfunction "C2-_5") (pintype "bidirectional"))
    )
    (net (code "31") (name "Net-(IC1A-V+)") (class "Default")
      (node (ref "C4") (pin "1") (pinfunction "1_1") (pintype "passive"))
      (node (ref "IC1") (pin "2") (pinfunction "V+_2") (pintype "bidirectional"))
    )
    (net (code "32") (name "Net-(IC1A-V-)") (class "Default")
      (node (ref "C5") (pin "1") (pinfunction "1_1") (pintype "passive"))
      (node (ref "IC1") (pin "6") (pinfunction "V-_6") (pintype "bidirectional"))
    )
    (net (code "33") (name "Net-(IC2-PK0(A0{slash}A8{slash}A16))") (class "Default")
      (node (ref "IC2") (pin "75") (pinfunction "PK0(A0/A8/A16)_75") (pintype "bidirectional"))
      (node (ref "R9") (pin "1") (pinfunction "1_1") (pintype "bidirectional"))
    )
    (net (code "34") (name "Net-(IC2-PK1(A1{slash}A9{slash}A17))") (class "Default")
      (node (ref "IC2") (pin "76") (pinfunction "PK1(A1/A9/A17)_76") (pintype "bidirectional"))
      (node (ref "R10") (pin "1") (pinfunction "1_1") (pintype "bidirectional"))
    )
    (net (code "35") (name "Net-(IC2-PK2(A2{slash}A10{slash}A18))") (class "Default")
      (node (ref "IC2") (pin "77") (pinfunction "PK2(A2/A10/A18)_77") (pintype "bidirectional"))
      (node (ref "R11") (pin "1") (pinfunction "1_1") (pintype "bidirectional"))
    )
    (net (code "36") (name "Net-(IC5-FB)") (class "Default")
      (node (ref "IC5") (pin "4") (pinfunction "FB_4") (pintype "input"))
      (node (ref "R12") (pin "1") (pinfunction "1_1") (pintype "bidirectional"))
      (node (ref "R25") (pin "2") (pinfunction "2_2") (pintype "bidirectional"))
    )
    (net (code "37") (name "Net-(IC5-OUT)") (class "Default")
      (node (ref "D1") (pin "C") (pinfunction "C_C") (pintype "passive"))
      (node (ref "IC5") (pin "2") (pinfunction "OUT_2") (pintype "output"))
      (node (ref "L1") (pin "1") (pinfunction "1_1") (pintype "passive"))
    )
    (net (code "38") (name "Net-(IC12-FB)") (class "Default")
      (node (ref "IC12") (pin "4") (pinfunction "FB_4") (pintype "input"))
      (node (ref "R24") (pin "2") (pinfunction "2_2") (pintype "bidirectional"))
      (node (ref "R27") (pin "1") (pinfunction "1_1") (pintype "bidirectional"))
    )
    (net (code "39") (name "Net-(IC12-OUT)") (class "Default")
      (node (ref "D2") (pin "C") (pinfunction "C_C") (pintype "passive"))
      (node (ref "IC12") (pin "2") (pinfunction "OUT_2") (pintype "output"))
      (node (ref "L2") (pin "1") (pinfunction "1_1") (pintype "passive"))
    )
    (net (code "40") (name "Net-(L_A0-PadA)") (class "Default")
      (node (ref "L_A0") (pin "A") (pinfunction "A_A") (pintype "passive"))
      (node (ref "R5") (pin "2") (pinfunction "2_2") (pintype "bidirectional"))
    )
    (net (code "41") (name "Net-(L_A1-PadA)") (class "Default")
      (node (ref "L_A1") (pin "A") (pinfunction "A_A") (pintype "passive"))
      (node (ref "R6") (pin "2") (pinfunction "2_2") (pintype "bidirectional"))
    )
    (net (code "42") (name "Net-(L_A2-PadA)") (class "Default")
      (node (ref "L_A2") (pin "A") (pinfunction "A_A") (pintype "passive"))
      (node (ref "R7") (pin "2") (pinfunction "2_2") (pintype "bidirectional"))
    )
    (net (code "43") (name "Net-(L_A3-PadA)") (class "Default")
      (node (ref "L_A3") (pin "A") (pinfunction "A_A") (pintype "passive"))
      (node (ref "R8") (pin "2") (pinfunction "2_2") (pintype "bidirectional"))
    )
    (net (code "44") (name "Net-(R9-Pad2)") (class "Default")
      (node (ref "R9") (pin "2") (pinfunction "2_2") (pintype "bidirectional"))
      (node (ref "RUN") (pin "A") (pinfunction "A_A") (pintype "passive"))
    )
    (net (code "45") (name "PA0") (class "Default")
      (node (ref "IC2") (pin "95") (pinfunction "PA0(ADCA0/AREFA)_95") (pintype "bidirectional"))
      (node (ref "R5") (pin "1") (pinfunction "1_1") (pintype "bidirectional"))
    )
    (net (code "46") (name "PA1") (class "Default")
      (node (ref "IC2") (pin "96") (pinfunction "PA1(ADCA1)_96") (pintype "bidirectional"))
      (node (ref "R6") (pin "1") (pinfunction "1_1") (pintype "bidirectional"))
    )
    (net (code "47") (name "PA2") (class "Default")
      (node (ref "IC2") (pin "97") (pinfunction "PA2(ADCA2)_97") (pintype "bidirectional"))
      (node (ref "R7") (pin "1") (pinfunction "1_1") (pintype "bidirectional"))
    )
    (net (code "48") (name "PA3") (class "Default")
      (node (ref "IC2") (pin "98") (pinfunction "PA3(ADCA3)_98") (pintype "bidirectional"))
      (node (ref "R8") (pin "1") (pinfunction "1_1") (pintype "bidirectional"))
    )
    (net (code "49") (name "PC0_3V3") (class "Default")
      (node (ref "IC2") (pin "15") (pinfunction "PC0(OC0A/SDA)_15") (pintype "bidirectional"))
    )
    (net (code "50") (name "PC1_3V3") (class "Default")
      (node (ref "IC2") (pin "16") (pinfunction "PC1(OC0B/XCK0/SCL)_16") (pintype "bidirectional"))
    )
    (net (code "51") (name "PC2_3V3") (class "Default")
      (node (ref "IC2") (pin "17") (pinfunction "PC2(OC0C/RXD0)_17") (pintype "bidirectional"))
    )
    (net (code "52") (name "PC3_3V3") (class "Default")
      (node (ref "IC2") (pin "18") (pinfunction "PC3(OC0D/TXD0)_18") (pintype "bidirectional"))
    )
    (net (code "53") (name "PDI_DATA_3V3") (class "Default")
      (node (ref "IC2") (pin "89") (pinfunction "PDI-DATA_89") (pintype "bidirectional"))
      (node (ref "PDI_ATMEL") (pin "1") (pinfunction "DATA_1") (pintype "passive"))
    )
    (net (code "54") (name "PW") (class "Default")
      (node (ref "C42") (pin "+") (pinfunction "+_+") (pintype "passive"))
      (node (ref "C43") (pin "+") (pinfunction "+_+") (pintype "passive"))
      (node (ref "D3") (pin "4") (pinfunction "C_4") (pintype "passive"))
      (node (ref "IC12") (pin "1") (pinfunction "IN_1") (pintype "input"))
      (node (ref "IC5") (pin "1") (pinfunction "IN_1") (pintype "input"))
    )
    (net (code "55") (name "PWM_D0_3V3") (class "Default")
      (node (ref "IC2") (pin "25") (pinfunction "PD0(OC0A/SDA)_25") (pintype "bidirectional"))
      (node (ref "IC6") (pin "21") (pinfunction "IO_VL0_21") (pintype "bidirectional"))
    )
    (net (code "56") (name "PWM_D0_5V") (class "Default")
      (node (ref "IC6") (pin "3") (pinfunction "IO_VCC0_3") (pintype "bidirectional"))
      (node (ref "PWMD0") (pin "3") (pinfunction "3_3") (pintype "passive"))
    )
    (net (code "57") (name "PWM_D1_3V3") (class "Default")
      (node (ref "IC2") (pin "26") (pinfunction "PD1(OC0B/XCK0/SCL)_26") (pintype "bidirectional"))
      (node (ref "IC6") (pin "20") (pinfunction "IO_VL1_20") (pintype "bidirectional"))
    )
    (net (code "58") (name "PWM_D1_5V") (class "Default")
      (node (ref "IC6") (pin "4") (pinfunction "IO_VCC1_4") (pintype "bidirectional"))
      (node (ref "PWMD1") (pin "3") (pinfunction "3_3") (pintype "passive"))
    )
    (net (code "59") (name "PWM_D2_3V3") (class "Default")
      (node (ref "IC2") (pin "27") (pinfunction "PD2(OC0C/RXD0)_27") (pintype "bidirectional"))
      (node (ref "IC6") (pin "19") (pinfunction "IO_VL2_19") (pintype "bidirectional"))
    )
    (net (code "60") (name "PWM_D2_5V") (class "Default")
      (node (ref "IC6") (pin "5") (pinfunction "IO_VCC2_5") (pintype "bidirectional"))
      (node (ref "PWMD2") (pin "3") (pinfunction "3_3") (pintype "passive"))
    )
    (net (code "61") (name "PWM_D3_3V3") (class "Default")
      (node (ref "IC2") (pin "28") (pinfunction "PD3(OC0D/TXD0)_28") (pintype "bidirectional"))
      (node (ref "IC6") (pin "18") (pinfunction "IO_VL3_18") (pintype "bidirectional"))
    )
    (net (code "62") (name "PWM_D3_5V") (class "Default")
      (node (ref "IC6") (pin "6") (pinfunction "IO_VCC3_6") (pintype "bidirectional"))
      (node (ref "PWMD3") (pin "3") (pinfunction "3_3") (pintype "passive"))
    )
    (net (code "63") (name "PWM_D4_3V3") (class "Default")
      (node (ref "IC2") (pin "29") (pinfunction "PD4(OC1A/~{SS})_29") (pintype "bidirectional"))
      (node (ref "IC6") (pin "17") (pinfunction "IO_VL4_17") (pintype "bidirectional"))
    )
    (net (code "64") (name "PWM_D4_5V") (class "Default")
      (node (ref "IC6") (pin "7") (pinfunction "IO_VCC4_7") (pintype "bidirectional"))
      (node (ref "PWMD4") (pin "3") (pinfunction "3_3") (pintype "passive"))
    )
    (net (code "65") (name "PWM_D5_3V3") (class "Default")
      (node (ref "IC2") (pin "30") (pinfunction "PD5(OC1B/XCK1/MOSI)_30") (pintype "bidirectional"))
      (node (ref "IC6") (pin "16") (pinfunction "IO_VL5_16") (pintype "bidirectional"))
    )
    (net (code "66") (name "PWM_D5_5V") (class "Default")
      (node (ref "IC6") (pin "8") (pinfunction "IO_VCC5_8") (pintype "bidirectional"))
      (node (ref "PWMD5") (pin "3") (pinfunction "3_3") (pintype "passive"))
    )
    (net (code "67") (name "RX_3V3") (class "Default")
      (node (ref "IC1") (pin "12") (pinfunction "R1OUT_12") (pintype "output"))
      (node (ref "IC2") (pin "47") (pinfunction "PF2(OC0C/RXD0)_47") (pintype "bidirectional"))
      (node (ref "R13") (pin "2") (pinfunction "2_2") (pintype "bidirectional"))
      (node (ref "R3") (pin "1") (pinfunction "1_1") (pintype "bidirectional"))
    )
    (net (code "68") (name "RX_232") (class "Default")
      (node (ref "IC1") (pin "13") (pinfunction "R1IN_13") (pintype "input"))
      (node (ref "R13") (pin "1") (pinfunction "1_1") (pintype "bidirectional"))
      (node (ref "UART") (pin "3") (pinfunction "S_3") (pintype "passive"))
    )
    (net (code "69") (name "RX_CAM_3V3") (class "Default")
      (node (ref "IC2") (pin "51") (pinfunction "PF6(RXD1/MISO)_51") (pintype "bidirectional"))
      (node (ref "R18") (pin "1") (pinfunction "1_1") (pintype "bidirectional"))
      (node (ref "UART_CAM") (pin "2") (pinfunction "S_2") (pintype "passive"))
    )
    (net (code "70") (name "RX_COLOR_SENSOR_3V3") (class "Default")
      (node (ref "IC2") (pin "31") (pinfunction "PD6(RXD1/MISO)_31") (pintype "bidirectional"))
    )
    (net (code "71") (name "SCK_ENCODER_3V3") (class "Default")
      (node (ref "IC2") (pin "42") (pinfunction "PE7(TSD1/SCK/CLKO/EVO/TOSC1)_42") (pintype "bidirectional"))
    )
    (net (code "72") (name "TX_3V3") (class "Default")
      (node (ref "IC1") (pin "10") (pinfunction "T2IN_10") (pintype "input"))
      (node (ref "IC1") (pin "11") (pinfunction "T1IN_11") (pintype "input"))
      (node (ref "IC2") (pin "48") (pinfunction "PF3(OC0D/TXD0)_48") (pintype "bidirectional"))
      (node (ref "R14") (pin "2") (pinfunction "2_2") (pintype "bidirectional"))
      (node (ref "R4") (pin "1") (pinfunction "1_1") (pintype "bidirectional"))
    )
    (net (code "73") (name "TX_232") (class "Default")
      (node (ref "IC1") (pin "14") (pinfunction "T1OUT_14") (pintype "output"))
      (node (ref "R14") (pin "1") (pinfunction "1_1") (pintype "bidirectional"))
      (node (ref "UART") (pin "4") (pinfunction "S_4") (pintype "passive"))
    )
    (net (code "74") (name "TX_CAM_3V3") (class "Default")
      (node (ref "IC2") (pin "52") (pinfunction "PF7(TXD1/SCK)_52") (pintype "bidirectional"))
      (node (ref "R19") (pin "1") (pinfunction "1_1") (pintype "bidirectional"))
      (node (ref "UART_CAM") (pin "3") (pinfunction "S_3") (pintype "passive"))
    )
    (net (code "75") (name "TX_COLOR_SENSOR_3V3") (class "Default")
      (node (ref "IC2") (pin "32") (pinfunction "PD7(TXD1/SCK/CLKO/EVO)_32") (pintype "bidirectional"))
    )
    (net (code "76") (name "VACCUM_PRESSURE_0_0-1V") (class "Default")
      (node (ref "IC2") (pin "99") (pinfunction "PA4(ADCA4)_99") (pintype "bidirectional"))
    )
    (net (code "77") (name "VACCUM_PRESSURE_1_0-1V") (class "Default")
      (node (ref "IC2") (pin "100") (pinfunction "PA5(ADCA5)_100") (pintype "bidirectional"))
    )
    (net (code "78") (name "VACUUM_PUMP_0_VOLTAGE_MONITOR_0-1V") (class "Default")
      (node (ref "IC2") (pin "1") (pinfunction "PA6(ADCA6)_1") (pintype "bidirectional"))
    )
    (net (code "79") (name "VACUUM_PUMP_1_VOLTAGE_MONITOR_0-1V") (class "Default")
      (node (ref "IC2") (pin "2") (pinfunction "PA7/(ADCA7/AC0-OUT)_2") (pintype "bidirectional"))
    )
    (net (code "80") (name "unconnected-(IC1A-R2OUT-Pad9)") (class "Default")
      (node (ref "IC1") (pin "9") (pinfunction "R2OUT_9") (pintype "output"))
    )
    (net (code "81") (name "unconnected-(IC1A-T2OUT-Pad7)") (class "Default")
      (node (ref "IC1") (pin "7") (pinfunction "T2OUT_7") (pintype "output"))
    )
    (net (code "82") (name "unconnected-(IC2-PB4(ADCB4{slash}TMS)-Pad9)") (class "Default")
      (node (ref "IC2") (pin "9") (pinfunction "PB4(ADCB4/TMS)_9") (pintype "bidirectional"))
    )
    (net (code "83") (name "unconnected-(IC2-PB5(ADCB5{slash}TDI)-Pad10)") (class "Default")
      (node (ref "IC2") (pin "10") (pinfunction "PB5(ADCB5/TDI)_10") (pintype "bidirectional"))
    )
    (net (code "84") (name "unconnected-(IC2-PB6(ADCB6{slash}TCK)-Pad11)") (class "Default")
      (node (ref "IC2") (pin "11") (pinfunction "PB6(ADCB6/TCK)_11") (pintype "bidirectional"))
    )
    (net (code "85") (name "unconnected-(IC2-PB7(ADCB7{slash}AC0-OUT{slash}TDO)-Pad12)") (class "Default")
      (node (ref "IC2") (pin "12") (pinfunction "PB7(ADCB7/AC0-OUT/TDO)_12") (pintype "bidirectional"))
    )
    (net (code "86") (name "unconnected-(IC2-PC4(OC1A{slash}~{SS})-Pad19)") (class "Default")
      (node (ref "IC2") (pin "19") (pinfunction "PC4(OC1A/~{SS})_19") (pintype "bidirectional"))
    )
    (net (code "87") (name "unconnected-(IC2-PE4(OC1A{slash}~{SS})-Pad39)") (class "Default")
      (node (ref "IC2") (pin "39") (pinfunction "PE4(OC1A/~{SS})_39") (pintype "bidirectional"))
    )
    (net (code "88") (name "unconnected-(IC2-PF0(OC0A{slash}SDA)-Pad45)") (class "Default")
      (node (ref "IC2") (pin "45") (pinfunction "PF0(OC0A/SDA)_45") (pintype "bidirectional"))
    )
    (net (code "89") (name "unconnected-(IC2-PF1(OC0B{slash}XCK0{slash}SCL)-Pad46)") (class "Default")
      (node (ref "IC2") (pin "46") (pinfunction "PF1(OC0B/XCK0/SCL)_46") (pintype "bidirectional"))
    )
    (net (code "90") (name "unconnected-(IC2-PF4(OC1A{slash}~{SS})-Pad49)") (class "Default")
      (node (ref "IC2") (pin "49") (pinfunction "PF4(OC1A/~{SS})_49") (pintype "bidirectional"))
    )
    (net (code "91") (name "unconnected-(IC2-PF5(OC1B{slash}XCK1{slash}MOSI)-Pad50)") (class "Default")
      (node (ref "IC2") (pin "50") (pinfunction "PF5(OC1B/XCK1/MOSI)_50") (pintype "bidirectional"))
    )
    (net (code "92") (name "unconnected-(IC2-PH4(BA0{slash}~{CS0}{slash}A16)-Pad59)") (class "Default")
      (node (ref "IC2") (pin "59") (pinfunction "PH4(BA0/~{CS0}/A16)_59") (pintype "bidirectional"))
    )
    (net (code "93") (name "unconnected-(IC2-PH5(BA1{slash}~{CS1}{slash}A17)-Pad60)") (class "Default")
      (node (ref "IC2") (pin "60") (pinfunction "PH5(BA1/~{CS1}/A17)_60") (pintype "bidirectional"))
    )
    (net (code "94") (name "unconnected-(IC2-PH6(CKE{slash}~{CS2}{slash}A18)-Pad61)") (class "Default")
      (node (ref "IC2") (pin "61") (pinfunction "PH6(CKE/~{CS2}/A18)_61") (pintype "bidirectional"))
    )
    (net (code "95") (name "unconnected-(IC2-PH7(CLK{slash}~{CS3}{slash}A19)-Pad62)") (class "Default")
      (node (ref "IC2") (pin "62") (pinfunction "PH7(CLK/~{CS3}/A19)_62") (pintype "bidirectional"))
    )
    (net (code "96") (name "unconnected-(IC2-PJ0(D0{slash}A0{slash}A8)-Pad65)") (class "Default")
      (node (ref "IC2") (pin "65") (pinfunction "PJ0(D0/A0/A8)_65") (pintype "bidirectional"))
    )
    (net (code "97") (name "unconnected-(IC2-PJ1(D1{slash}A1{slash}A9)-Pad66)") (class "Default")
      (node (ref "IC2") (pin "66") (pinfunction "PJ1(D1/A1/A9)_66") (pintype "bidirectional"))
    )
    (net (code "98") (name "unconnected-(IC2-PJ2(D2{slash}A2{slash}A10)-Pad67)") (class "Default")
      (node (ref "IC2") (pin "67") (pinfunction "PJ2(D2/A2/A10)_67") (pintype "bidirectional"))
    )
    (net (code "99") (name "unconnected-(IC2-PJ3(D3{slash}A3{slash}A11)-Pad68)") (class "Default")
      (node (ref "IC2") (pin "68") (pinfunction "PJ3(D3/A3/A11)_68") (pintype "bidirectional"))
    )
    (net (code "100") (name "unconnected-(IC2-PJ4(A8{slash}D4{slash}A4{slash}A12)-Pad69)") (class "Default")
      (node (ref "IC2") (pin "69") (pinfunction "PJ4(A8/D4/A4/A12)_69") (pintype "bidirectional"))
    )
    (net (code "101") (name "unconnected-(IC2-PJ5(A9{slash}D5{slash}A5{slash}A13)-Pad70)") (class "Default")
      (node (ref "IC2") (pin "70") (pinfunction "PJ5(A9/D5/A5/A13)_70") (pintype "bidirectional"))
    )
    (net (code "102") (name "unconnected-(IC2-PJ6(A10{slash}D6{slash}A6{slash}A14)-Pad71)") (class "Default")
      (node (ref "IC2") (pin "71") (pinfunction "PJ6(A10/D6/A6/A14)_71") (pintype "bidirectional"))
    )
    (net (code "103") (name "unconnected-(IC2-PJ7(A11{slash}D7{slash}A7{slash}A15)-Pad72)") (class "Default")
      (node (ref "IC2") (pin "72") (pinfunction "PJ7(A11/D7/A7/A15)_72") (pintype "bidirectional"))
    )
    (net (code "104") (name "unconnected-(IC2-PK3(A3{slash}A11{slash}A19)-Pad78)") (class "Default")
      (node (ref "IC2") (pin "78") (pinfunction "PK3(A3/A11/A19)_78") (pintype "bidirectional"))
    )
    (net (code "105") (name "unconnected-(IC2-PK4(A4{slash}A12{slash}A20)-Pad79)") (class "Default")
      (node (ref "IC2") (pin "79") (pinfunction "PK4(A4/A12/A20)_79") (pintype "bidirectional"))
    )
    (net (code "106") (name "unconnected-(IC2-PK5(A5{slash}A13{slash}A22)-Pad80)") (class "Default")
      (node (ref "IC2") (pin "80") (pinfunction "PK5(A5/A13/A22)_80") (pintype "bidirectional"))
    )
    (net (code "107") (name "unconnected-(IC2-PK6(A6{slash}A14{slash}A22)-Pad81)") (class "Default")
      (node (ref "IC2") (pin "81") (pinfunction "PK6(A6/A14/A22)_81") (pintype "bidirectional"))
    )
    (net (code "108") (name "unconnected-(IC2-PK7(A7{slash}A15{slash}A23)-Pad82)") (class "Default")
      (node (ref "IC2") (pin "82") (pinfunction "PK7(A7/A15/A23)_82") (pintype "bidirectional"))
    )
    (net (code "109") (name "unconnected-(IC2-PQ1(TOSC2)-Pad86)") (class "Default")
      (node (ref "IC2") (pin "86") (pinfunction "PQ1(TOSC2)_86") (pintype "bidirectional"))
    )
    (net (code "110") (name "unconnected-(IC2-PQ2-Pad87)") (class "Default")
      (node (ref "IC2") (pin "87") (pinfunction "PQ2_87") (pintype "bidirectional"))
    )
    (net (code "111") (name "unconnected-(IC2-PQ3-Pad88)") (class "Default")
      (node (ref "IC2") (pin "88") (pinfunction "PQ3_88") (pintype "bidirectional"))
    )
    (net (code "112") (name "unconnected-(IC2-PR0(XTAL2)-Pad91)") (class "Default")
      (node (ref "IC2") (pin "91") (pinfunction "PR0(XTAL2)_91") (pintype "bidirectional"))
    )
    (net (code "113") (name "unconnected-(IC2-PR1(XTAL1)-Pad92)") (class "Default")
      (node (ref "IC2") (pin "92") (pinfunction "PR1(XTAL1)_92") (pintype "bidirectional"))
    )
    (net (code "114") (name "unconnected-(IC6-IO_VCC6-Pad9)") (class "Default")
      (node (ref "IC6") (pin "9") (pinfunction "IO_VCC6_9") (pintype "bidirectional"))
    )
    (net (code "115") (name "unconnected-(IC6-IO_VCC7-Pad10)") (class "Default")
      (node (ref "IC6") (pin "10") (pinfunction "IO_VCC7_10") (pintype "bidirectional"))
    )
    (net (code "116") (name "unconnected-(IC6-IO_VL6-Pad15)") (class "Default")
      (node (ref "IC6") (pin "15") (pinfunction "IO_VL6_15") (pintype "bidirectional"))
    )
    (net (code "117") (name "unconnected-(PDI_ATMEL-NC-Pad3)") (class "Default")
      (node (ref "PDI_ATMEL") (pin "3") (pinfunction "NC_3") (pintype "passive"))
    )
    (net (code "118") (name "unconnected-(PDI_ATMEL-NC.-Pad4)") (class "Default")
      (node (ref "PDI_ATMEL") (pin "4") (pinfunction "NC._4") (pintype "passive"))
    )
    (net (code "119") (name "unconnected-(UARTA-S-Pad1)") (class "Default")
      (node (ref "UART") (pin "1") (pinfunction "S_1") (pintype "passive"))
    )
    (net (code "120") (name "{slash}RESET_3V3") (class "Default")
      (node (ref "IC2") (pin "90") (pinfunction "PDI-CLK/~{RESET}_90") (pintype "input"))
      (node (ref "PDI_ATMEL") (pin "5") (pinfunction "CLK_5") (pintype "passive"))
      (node (ref "R15") (pin "2") (pinfunction "2_2") (pintype "bidirectional"))
    )
  )
)
